# driver.net
KiCad netlist of a schematic drawn in EAGLE
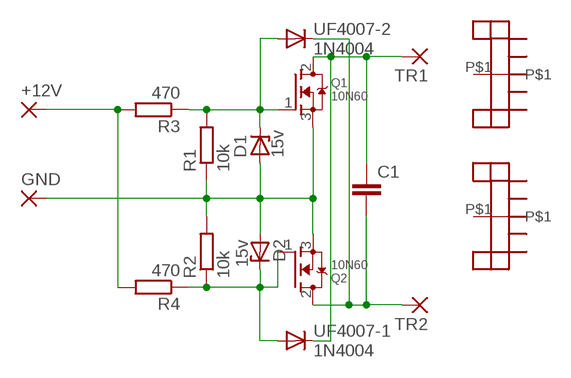
[diagram p0: schematic, sheet 1]

(export (version "E")
  (design (tool "Eeschema 10.0.6"))
  (components
    (comp (ref "+12V")
      (value "3,17/1,1")
      (footprint "eagle-import:3,17_1,1")
      (libsource (lib "eagle-import") (part "3,17/1,1"))
    )
    (comp (ref "C1")
      (value "C-EU150-064X183")
      (footprint "eagle-import:C150-064X183")
      (libsource (lib "eagle-import") (part "C-EU150-064X183"))
    )
    (comp (ref "D1")
      (value "15v")
      (footprint "eagle-import:DO35Z10")
      (libsource (lib "eagle-import") (part "ZENER-DIODEDO35Z10"))
    )
    (comp (ref "D2")
      (value "15v")
      (footprint "eagle-import:DO35Z10")
      (libsource (lib "eagle-import") (part "ZENER-DIODEDO35Z10"))
    )
    (comp (ref "GND")
      (value "3,17/1,1")
      (footprint "eagle-import:3,17_1,1")
      (libsource (lib "eagle-import") (part "3,17/1,1"))
    )
    (comp (ref "Q1")
      (value "10N60")
      (footprint "eagle-import:TO220V")
      (libsource (lib "eagle-import") (part "MOSFET-NGDS_TO220V"))
    )
    (comp (ref "Q2")
      (value "10N60")
      (footprint "eagle-import:TO220V")
      (libsource (lib "eagle-import") (part "MOSFET-NGDS_TO220V"))
    )
    (comp (ref "R1")
      (value "10k")
      (footprint "eagle-import:0204_7")
      (libsource (lib "eagle-import") (part "R-EU_0204/7"))
    )
    (comp (ref "R2")
      (value "10k")
      (footprint "eagle-import:0204_7")
      (libsource (lib "eagle-import") (part "R-EU_0204/7"))
    )
    (comp (ref "R3")
      (value "470")
      (footprint "eagle-import:0617_17")
      (libsource (lib "eagle-import") (part "R-EU_0617/17"))
    )
    (comp (ref "R4")
      (value "470")
      (footprint "eagle-import:0617_17")
      (libsource (lib "eagle-import") (part "R-EU_0617/17"))
    )
    (comp (ref "TR1")
      (value "3,17/1,1")
      (footprint "eagle-import:3,17_1,1")
      (libsource (lib "eagle-import") (part "3,17/1,1"))
    )
    (comp (ref "TR2")
      (value "3,17/1,1")
      (footprint "eagle-import:3,17_1,1")
      (libsource (lib "eagle-import") (part "3,17/1,1"))
    )
    (comp (ref "U$1")
      (value "RADIATOR")
      (footprint "eagle-import:RAD15X11")
      (libsource (lib "eagle-import") (part "RADIATOR"))
    )
    (comp (ref "U$2")
      (value "RADIATOR")
      (footprint "eagle-import:RAD15X11")
      (libsource (lib "eagle-import") (part "RADIATOR"))
    )
    (comp (ref "UF4007-1")
      (value "1N4004")
      (footprint "eagle-import:DO41-10")
      (libsource (lib "eagle-import") (part "1N4004"))
    )
    (comp (ref "UF4007-2")
      (value "1N4004")
      (footprint "eagle-import:DO41-10")
      (libsource (lib "eagle-import") (part "1N4004"))
    )
  )
  (nets
    (net (code "1") (name "Net-(+12V-P)") (class "Default")
      (node (ref "+12V") (pin "1") (pinfunction "P_1") (pintype "passive"))
      (node (ref "R3") (pin "2") (pinfunction "2_2") (pintype "passive"))
      (node (ref "R4") (pin "2") (pinfunction "2_2") (pintype "passive"))
    )
    (net (code "2") (name "Net-(GND-P)") (class "Default")
      (node (ref "D1") (pin "A") (pinfunction "A_A") (pintype "passive"))
      (node (ref "D2") (pin "A") (pinfunction "A_A") (pintype "passive"))
      (node (ref "GND") (pin "1") (pinfunction "P_1") (pintype "passive"))
      (node (ref "Q1") (pin "3") (pinfunction "S_3") (pintype "bidirectional"))
      (node (ref "Q2") (pin "3") (pinfunction "S_3") (pintype "bidirectional"))
      (node (ref "R1") (pin "1") (pinfunction "1_1") (pintype "passive"))
      (node (ref "R2") (pin "2") (pinfunction "2_2") (pintype "passive"))
    )
    (net (code "3") (name "Net-(Q1-D)") (class "Default")
      (node (ref "C1") (pin "1") (pinfunction "1_1") (pintype "passive"))
      (node (ref "Q1") (pin "2") (pinfunction "D_2") (pintype "bidirectional"))
      (node (ref "TR1") (pin "1") (pinfunction "P_1") (pintype "passive"))
      (node (ref "UF4007-1") (pin "C") (pinfunction "C_C") (pintype "passive"))
    )
    (net (code "4") (name "Net-(Q1-G)") (class "Default")
      (node (ref "D1") (pin "C") (pinfunction "C_C") (pintype "passive"))
      (node (ref "Q1") (pin "1") (pinfunction "G_1") (pintype "bidirectional"))
      (node (ref "R1") (pin "2") (pinfunction "2_2") (pintype "passive"))
      (node (ref "R3") (pin "1") (pinfunction "1_1") (pintype "passive"))
      (node (ref "UF4007-2") (pin "A") (pinfunction "A_A") (pintype "passive"))
    )
    (net (code "5") (name "Net-(Q2-D)") (class "Default")
      (node (ref "C1") (pin "2") (pinfunction "2_2") (pintype "passive"))
      (node (ref "Q2") (pin "2") (pinfunction "D_2") (pintype "bidirectional"))
      (node (ref "TR2") (pin "1") (pinfunction "P_1") (pintype "passive"))
      (node (ref "UF4007-2") (pin "C") (pinfunction "C_C") (pintype "passive"))
    )
    (net (code "6") (name "Net-(Q2-G)") (class "Default")
      (node (ref "D2") (pin "C") (pinfunction "C_C") (pintype "passive"))
      (node (ref "Q2") (pin "1") (pinfunction "G_1") (pintype "bidirectional"))
      (node (ref "R2") (pin "1") (pinfunction "1_1") (pintype "passive"))
      (node (ref "R4") (pin "1") (pinfunction "1_1") (pintype "passive"))
      (node (ref "UF4007-1") (pin "A") (pinfunction "A_A") (pintype "passive"))
    )
    (net (code "7") (name "unconnected-(U$1-PadP$1)") (class "Default")
      (node (ref "U$1") (pin "P$1") (pinfunction "P$1_P$1") (pintype "bidirectional"))
    )
    (net (code "8") (name "unconnected-(U$2-PadP$1)") (class "Default")
      (node (ref "U$2") (pin "P$1") (pinfunction "P$1_P$1") (pintype "bidirectional"))
    )
  )
)
